# Mcu.net
KiCad netlist of a schematic drawn in Altium Designer
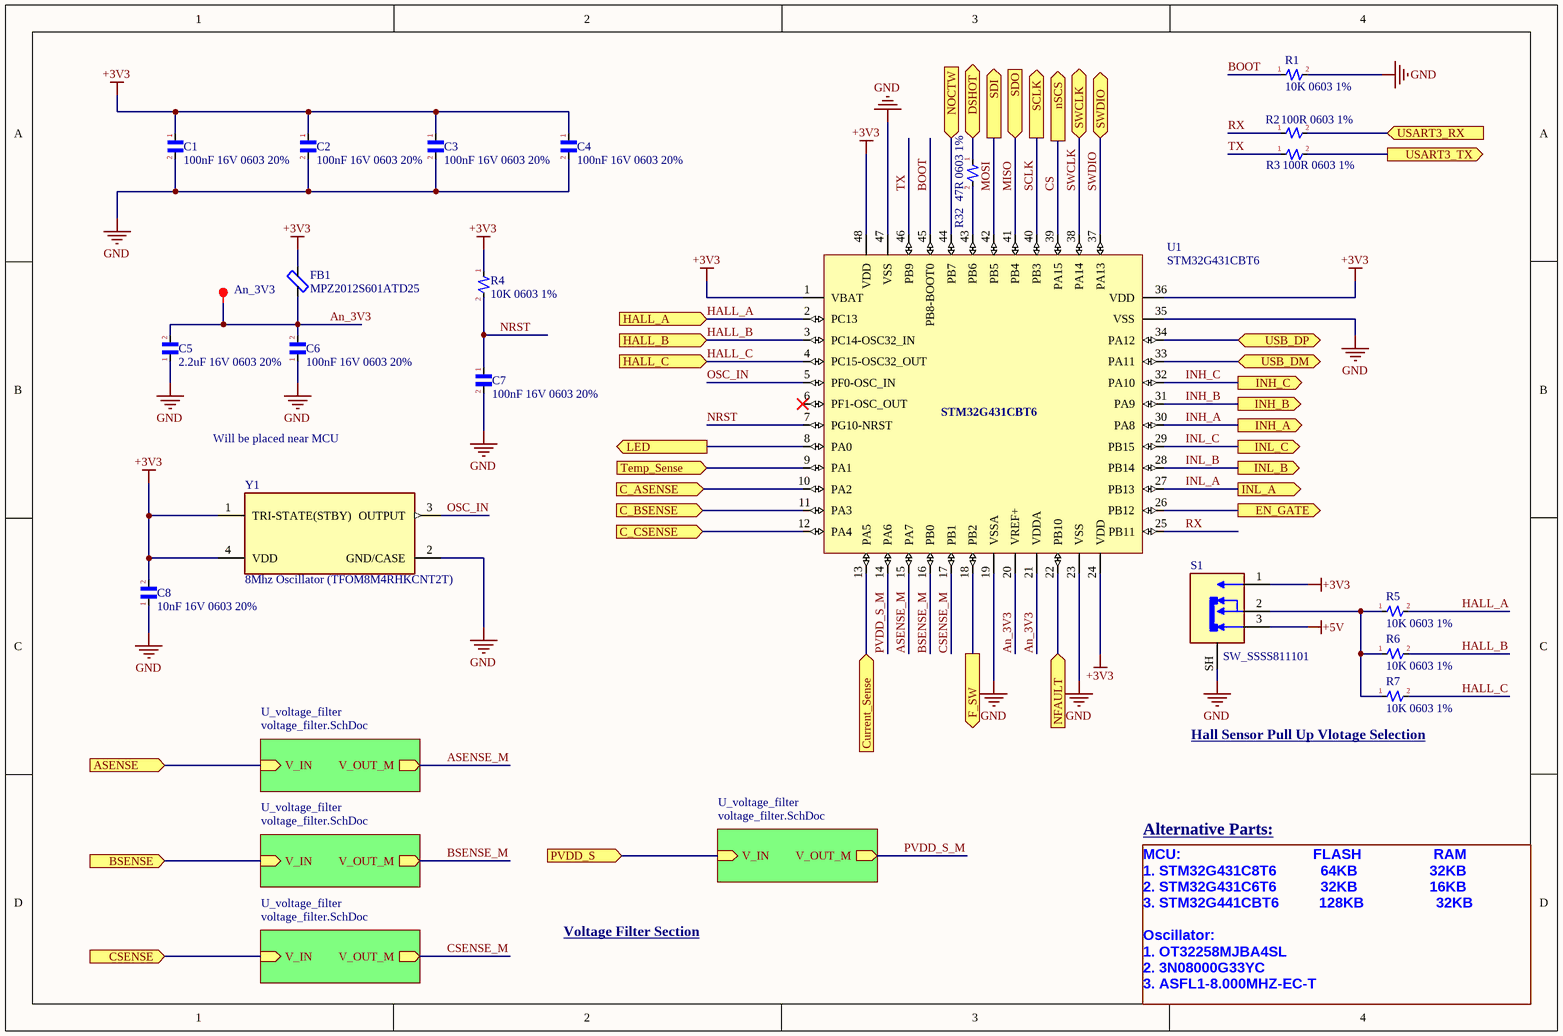
[diagram p0: Mcu.SchDoc]

(export (version "E")
  (design (tool "Eeschema 10.0.6"))
  (components
    (comp (ref "C1")
      (value "100nF 16V 0603 20%")
      (footprint "C_0603")
      (description "CAP  0603 20%")
      (libsource (lib "") (part "Capacitor{gt}{gt} Non-Polar_1"))
    )
    (comp (ref "C2")
      (value "100nF 16V 0603 20%")
      (footprint "C_0603")
      (description "CAP  0603 20%")
      (libsource (lib "") (part "Capacitor{gt}{gt} Non-Polar_1"))
    )
    (comp (ref "C3")
      (value "100nF 16V 0603 20%")
      (footprint "C_0603")
      (description "CAP  0603 20%")
      (libsource (lib "") (part "Capacitor{gt}{gt} Non-Polar_1"))
    )
    (comp (ref "C4")
      (value "100nF 16V 0603 20%")
      (footprint "C_0603")
      (description "CAP  0603 20%")
      (libsource (lib "") (part "Capacitor{gt}{gt} Non-Polar_1"))
    )
    (comp (ref "C5")
      (value "2.2uF 16V 0603 20%")
      (footprint "C_0603")
      (description "CAP  0603 20%")
      (libsource (lib "Walton_EED") (part "Capacitor{gt}{gt} Non-Polar"))
    )
    (comp (ref "C6")
      (value "100nF 16V 0603 20%")
      (footprint "C_0603")
      (description "CAP  0603 20%")
      (libsource (lib "Walton_EED") (part "Capacitor{gt}{gt} Non-Polar"))
    )
    (comp (ref "C7")
      (value "100nF 16V 0603 20%")
      (footprint "C_0603")
      (description "CAP  0603 20%")
      (libsource (lib "") (part "Capacitor{gt}{gt} Non-Polar_1"))
    )
    (comp (ref "C8")
      (value "10nF 16V 0603 20%")
      (footprint "C_0603")
      (description "CAP  0603 20%")
      (libsource (lib "Walton_EED") (part "Capacitor{gt}{gt} Non-Polar"))
    )
    (comp (ref "FB1")
      (value "MPZ2012S601ATD25")
      (footprint "BEADC2012X105N")
      (description "600 Ohms @ 100MHz 1 Power Line Ferrite Bead 0805 (2012 Metric) 2A 100mOhm")
      (fields (field (name "MF") "TDK"))
      (libsource (lib "Walton_EED_13_05_2024") (part "FB{gt}{gt}MPZ2012S601ATD25"))
    )
    (comp (ref "R1")
      (value "10K 0603 1%")
      (footprint "R_0603")
      (description "RES 0603 20%")
      (libsource (lib "Walton_EED") (part "Resistor{gt}{gt} General Purpose"))
    )
    (comp (ref "R2")
      (value "100R 0603 1%")
      (footprint "R_0603")
      (description "RES 0603 20%")
      (libsource (lib "Walton_EED") (part "Resistor{gt}{gt} General Purpose"))
    )
    (comp (ref "R3")
      (value "100R 0603 1%")
      (footprint "R_0603")
      (description "RES 0603 20%")
      (libsource (lib "Walton_EED") (part "Resistor{gt}{gt} General Purpose"))
    )
    (comp (ref "R4")
      (value "10K 0603 1%")
      (footprint "R_0603")
      (description "RES 0603 20%")
      (libsource (lib "Walton_EED") (part "Resistor{gt}{gt} General Purpose"))
    )
    (comp (ref "R5")
      (value "10K 0603 1%")
      (footprint "R_0603")
      (description "RES 0603 20%")
      (libsource (lib "Walton_EED") (part "Resistor{gt}{gt} General Purpose"))
    )
    (comp (ref "R6")
      (value "10K 0603 1%")
      (footprint "R_0603")
      (description "RES 0603 20%")
      (libsource (lib "Walton_EED") (part "Resistor{gt}{gt} General Purpose"))
    )
    (comp (ref "R7")
      (value "10K 0603 1%")
      (footprint "R_0603")
      (description "RES 0603 20%")
      (libsource (lib "Walton_EED") (part "Resistor{gt}{gt} General Purpose"))
    )
    (comp (ref "R32")
      (value "47R 0603 1%")
      (footprint "R_0603")
      (description "RES 0603 20%")
      (libsource (lib "Walton_EED") (part "Resistor{gt}{gt} General Purpose"))
    )
    (comp (ref "S1")
      (value "SW_SSSS811101")
      (footprint "SW_SSSS811101")
      (description "Switch Slide SP Side Slide 0.3A 5VDC 10000Cycles Gull Wing SMD T/R")
      (fields (field (name "MF") "ALPS") (field (name "MP") "SSSS811101"))
      (libsource (lib "Walton_EED_13_05_2024") (part "SW_SSSS811101"))
    )
    (comp (ref "TP44") (value "An_3V3") (footprint "TP_1mm_SMD") (libsource (lib "*") (part "Test point TP")))
    (comp (ref "U1")
      (value "STM32G431CBT6")
      (footprint "QFP50P900X900X160-48N")
      (libsource (lib "Walton_EED_13_05_2024") (part "STM32G431CBT6"))
    )
    (comp (ref "Y1")
      (value "8Mhz Oscillator (TFOM8M4RHKCNT2T)")
      (footprint "XTAL_ASE-8.000MHZ-LC-T")
      (description "8 MHz XO (Standard) CMOS Oscillator 3.3V Enable/Disable 4-SMD, No Lead")
      (fields (field (name "MF") "Abracon LLC") (field (name "MP") "ASE-8.000MHZ-LC-T"))
      (libsource (lib "Walton_EED_13_05_2024") (part "Osc{gt}{gt}ASE-8.000MHZ-LC-T"))
    )
  )
  (nets
    (net (code "1") (name "+3V3") (class "Default")
      (node (ref "C1") (pin "1") (pinfunction "1_1") (pintype "passive"))
      (node (ref "C2") (pin "1") (pinfunction "1_1") (pintype "passive"))
      (node (ref "C3") (pin "1") (pinfunction "1_1") (pintype "passive"))
      (node (ref "C4") (pin "1") (pinfunction "1_1") (pintype "passive"))
      (node (ref "C8") (pin "2") (pinfunction "2_2") (pintype "passive"))
      (node (ref "FB1") (pin "2") (pinfunction "2_2") (pintype "passive"))
      (node (ref "R4") (pin "1") (pinfunction "1_1") (pintype "passive"))
      (node (ref "S1") (pin "1") (pinfunction "1_1") (pintype "passive"))
      (node (ref "U1") (pin "1") (pinfunction "VBAT_1") (pintype "power_in"))
      (node (ref "U1") (pin "24") (pinfunction "VDD_24") (pintype "power_in"))
      (node (ref "U1") (pin "36") (pinfunction "VDD_36") (pintype "power_in"))
      (node (ref "U1") (pin "48") (pinfunction "VDD_48") (pintype "power_in"))
      (node (ref "Y1") (pin "1") (pinfunction "TRI-STATE(STBY)_1") (pintype "passive"))
      (node (ref "Y1") (pin "4") (pinfunction "VDD_4") (pintype "power_in"))
    )
    (net (code "2") (name "+5V") (class "Default")
      (node (ref "S1") (pin "3") (pinfunction "3_3") (pintype "passive"))
    )
    (net (code "4") (name "/ASENSE_M") (class "Default")
      (node (ref "U1") (pin "15") (pinfunction "PA7_15") (pintype "bidirectional"))
    )
    (net (code "5") (name "/An_3V3") (class "Default")
      (node (ref "C5") (pin "2") (pinfunction "2_2") (pintype "passive"))
      (node (ref "C6") (pin "2") (pinfunction "2_2") (pintype "passive"))
      (node (ref "FB1") (pin "1") (pinfunction "1_1") (pintype "passive"))
      (node (ref "TP44") (pin "1") (pinfunction "1_1") (pintype "passive"))
      (node (ref "U1") (pin "20") (pinfunction "VREF+_20") (pintype "passive"))
      (node (ref "U1") (pin "21") (pinfunction "VDDA_21") (pintype "power_in"))
    )
    (net (code "6") (name "/BOOT") (class "Default")
      (node (ref "R1") (pin "1") (pinfunction "1_1") (pintype "passive"))
      (node (ref "U1") (pin "45") (pinfunction "PB8-BOOT0_45") (pintype "bidirectional"))
    )
    (net (code "8") (name "/BSENSE_M") (class "Default")
      (node (ref "U1") (pin "16") (pinfunction "PB0_16") (pintype "bidirectional"))
    )
    (net (code "9") (name "/CS") (class "Default")
      (node (ref "U1") (pin "39") (pinfunction "PA15_39") (pintype "bidirectional"))
    )
    (net (code "11") (name "/CSENSE_M") (class "Default")
      (node (ref "U1") (pin "17") (pinfunction "PB1_17") (pintype "bidirectional"))
    )
    (net (code "12") (name "/C_ASENSE") (class "Default")
      (node (ref "U1") (pin "10") (pinfunction "PA2_10") (pintype "bidirectional"))
    )
    (net (code "13") (name "/C_BSENSE") (class "Default")
      (node (ref "U1") (pin "11") (pinfunction "PA3_11") (pintype "bidirectional"))
    )
    (net (code "14") (name "/C_CSENSE") (class "Default")
      (node (ref "U1") (pin "12") (pinfunction "PA4_12") (pintype "bidirectional"))
    )
    (net (code "15") (name "/Current_Sense") (class "Default")
      (node (ref "U1") (pin "13") (pinfunction "PA5_13") (pintype "bidirectional"))
    )
    (net (code "16") (name "/DSHOT") (class "Default")
      (node (ref "R32") (pin "1") (pinfunction "1_1") (pintype "passive"))
    )
    (net (code "17") (name "/EN_GATE") (class "Default")
      (node (ref "U1") (pin "26") (pinfunction "PB12_26") (pintype "bidirectional"))
    )
    (net (code "18") (name "/F_SW") (class "Default")
      (node (ref "U1") (pin "18") (pinfunction "PB2_18") (pintype "bidirectional"))
    )
    (net (code "19") (name "/HALL_A") (class "Default")
      (node (ref "R5") (pin "2") (pinfunction "2_2") (pintype "passive"))
      (node (ref "U1") (pin "2") (pinfunction "PC13_2") (pintype "bidirectional"))
    )
    (net (code "20") (name "/HALL_B") (class "Default")
      (node (ref "R6") (pin "2") (pinfunction "2_2") (pintype "passive"))
      (node (ref "U1") (pin "3") (pinfunction "PC14-OSC32_IN_3") (pintype "bidirectional"))
    )
    (net (code "21") (name "/HALL_C") (class "Default")
      (node (ref "R7") (pin "2") (pinfunction "2_2") (pintype "passive"))
      (node (ref "U1") (pin "4") (pinfunction "PC15-OSC32_OUT_4") (pintype "bidirectional"))
    )
    (net (code "22") (name "/INH_A") (class "Default")
      (node (ref "U1") (pin "30") (pinfunction "PA8_30") (pintype "bidirectional"))
    )
    (net (code "23") (name "/INH_B") (class "Default")
      (node (ref "U1") (pin "31") (pinfunction "PA9_31") (pintype "bidirectional"))
    )
    (net (code "24") (name "/INH_C") (class "Default")
      (node (ref "U1") (pin "32") (pinfunction "PA10_32") (pintype "bidirectional"))
    )
    (net (code "25") (name "/INL_A") (class "Default")
      (node (ref "U1") (pin "27") (pinfunction "PB13_27") (pintype "bidirectional"))
    )
    (net (code "26") (name "/INL_B") (class "Default")
      (node (ref "U1") (pin "28") (pinfunction "PB14_28") (pintype "bidirectional"))
    )
    (net (code "27") (name "/INL_C") (class "Default")
      (node (ref "U1") (pin "29") (pinfunction "PB15_29") (pintype "bidirectional"))
    )
    (net (code "28") (name "/LED") (class "Default")
      (node (ref "U1") (pin "8") (pinfunction "PA0_8") (pintype "bidirectional"))
    )
    (net (code "29") (name "/MISO") (class "Default")
      (node (ref "U1") (pin "41") (pinfunction "PB4_41") (pintype "bidirectional"))
    )
    (net (code "30") (name "/MOSI") (class "Default")
      (node (ref "U1") (pin "42") (pinfunction "PB5_42") (pintype "bidirectional"))
    )
    (net (code "31") (name "/NFAULT") (class "Default")
      (node (ref "U1") (pin "22") (pinfunction "PB10_22") (pintype "bidirectional"))
    )
    (net (code "32") (name "/NOCTW") (class "Default")
      (node (ref "U1") (pin "44") (pinfunction "PB7_44") (pintype "bidirectional"))
    )
    (net (code "33") (name "/NRST") (class "Default")
      (node (ref "C7") (pin "1") (pinfunction "1_1") (pintype "passive"))
      (node (ref "R4") (pin "2") (pinfunction "2_2") (pintype "passive"))
      (node (ref "U1") (pin "7") (pinfunction "PG10-NRST_7") (pintype "bidirectional"))
    )
    (net (code "34") (name "/OSC_IN") (class "Default")
      (node (ref "U1") (pin "5") (pinfunction "PF0-OSC_IN_5") (pintype "bidirectional"))
      (node (ref "Y1") (pin "3") (pinfunction "OUTPUT_3") (pintype "output"))
    )
    (net (code "36") (name "/PVDD_S_M") (class "Default")
      (node (ref "U1") (pin "14") (pinfunction "PA6_14") (pintype "bidirectional"))
    )
    (net (code "37") (name "/RX") (class "Default")
      (node (ref "R2") (pin "1") (pinfunction "1_1") (pintype "passive"))
      (node (ref "U1") (pin "25") (pinfunction "PB11_25") (pintype "bidirectional"))
    )
    (net (code "38") (name "/SCLK") (class "Default")
      (node (ref "U1") (pin "40") (pinfunction "PB3_40") (pintype "bidirectional"))
    )
    (net (code "39") (name "/SWCLK") (class "Default")
      (node (ref "U1") (pin "38") (pinfunction "PA14_38") (pintype "bidirectional"))
    )
    (net (code "40") (name "/SWDIO") (class "Default")
      (node (ref "U1") (pin "37") (pinfunction "PA13_37") (pintype "bidirectional"))
    )
    (net (code "41") (name "/TX") (class "Default")
      (node (ref "R3") (pin "1") (pinfunction "1_1") (pintype "passive"))
      (node (ref "U1") (pin "46") (pinfunction "PB9_46") (pintype "bidirectional"))
    )
    (net (code "42") (name "/Temp_Sense") (class "Default")
      (node (ref "U1") (pin "9") (pinfunction "PA1_9") (pintype "bidirectional"))
    )
    (net (code "43") (name "/USART3_RX") (class "Default")
      (node (ref "R2") (pin "2") (pinfunction "2_2") (pintype "passive"))
    )
    (net (code "44") (name "/USART3_TX") (class "Default")
      (node (ref "R3") (pin "2") (pinfunction "2_2") (pintype "passive"))
    )
    (net (code "45") (name "/USB_DM") (class "Default")
      (node (ref "U1") (pin "33") (pinfunction "PA11_33") (pintype "bidirectional"))
    )
    (net (code "46") (name "/USB_DP") (class "Default")
      (node (ref "U1") (pin "34") (pinfunction "PA12_34") (pintype "bidirectional"))
    )
    (net (code "47") (name "GND") (class "Default")
      (node (ref "C1") (pin "2") (pinfunction "2_2") (pintype "passive"))
      (node (ref "C2") (pin "2") (pinfunction "2_2") (pintype "passive"))
      (node (ref "C3") (pin "2") (pinfunction "2_2") (pintype "passive"))
      (node (ref "C4") (pin "2") (pinfunction "2_2") (pintype "passive"))
      (node (ref "C5") (pin "1") (pinfunction "1_1") (pintype "passive"))
      (node (ref "C6") (pin "1") (pinfunction "1_1") (pintype "passive"))
      (node (ref "C7") (pin "2") (pinfunction "2_2") (pintype "passive"))
      (node (ref "C8") (pin "1") (pinfunction "1_1") (pintype "passive"))
      (node (ref "R1") (pin "2") (pinfunction "2_2") (pintype "passive"))
      (node (ref "S1") (pin "SH") (pinfunction "4_SH") (pintype "passive"))
      (node (ref "U1") (pin "19") (pinfunction "VSSA_19") (pintype "power_in"))
      (node (ref "U1") (pin "23") (pinfunction "VSS_23") (pintype "power_in"))
      (node (ref "U1") (pin "35") (pinfunction "VSS_35") (pintype "power_in"))
      (node (ref "U1") (pin "47") (pinfunction "VSS_47") (pintype "power_in"))
      (node (ref "Y1") (pin "2") (pinfunction "GND/CASE_2") (pintype "power_in"))
    )
    (net (code "48") (name "Net-(R5-Pad1)") (class "Default")
      (node (ref "R5") (pin "1") (pinfunction "1_1") (pintype "passive"))
      (node (ref "R6") (pin "1") (pinfunction "1_1") (pintype "passive"))
      (node (ref "R7") (pin "1") (pinfunction "1_1") (pintype "passive"))
      (node (ref "S1") (pin "2") (pinfunction "2_2") (pintype "passive"))
    )
    (net (code "49") (name "Net-(U1-PB6)") (class "Default")
      (node (ref "R32") (pin "2") (pinfunction "2_2") (pintype "passive"))
      (node (ref "U1") (pin "43") (pinfunction "PB6_43") (pintype "bidirectional"))
    )
    (net (code "50") (name "unconnected-(U1-PF1-OSC_OUT-Pad6)") (class "Default")
      (node (ref "U1") (pin "6") (pinfunction "PF1-OSC_OUT_6") (pintype "bidirectional+no_connect"))
    )
  )
)
